# config_headers.net
KiCad netlist of a schematic drawn in Altium Designer
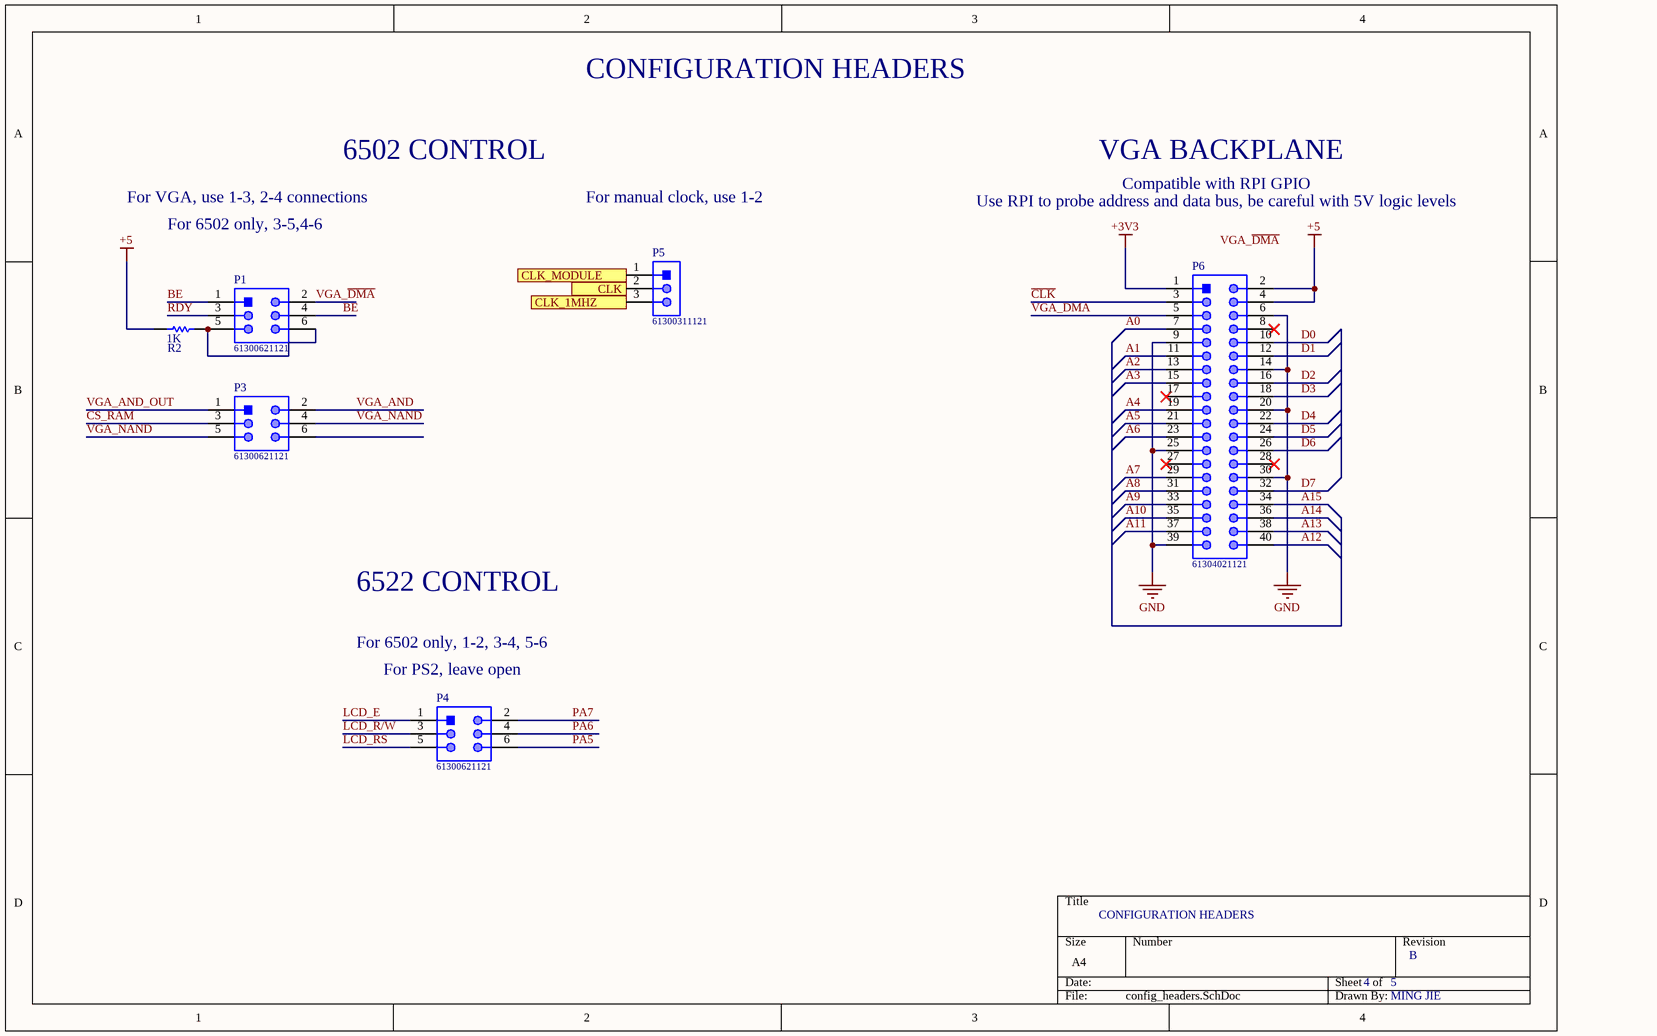
[diagram p0: config_headers.SchDoc]

(export (version "E")
  (design (tool "Eeschema 10.0.6"))
  (components
    (comp (ref "P1")
      (value "61300621121")
      (footprint "61300621121")
      (description "THT Vertical Pin Header WR-PHD, Pitch 2.54 mm, Dual Row, 6 pins")
      (fields (field (name "MANUFACTURER") "Wurth Elektronik") (field (name "PUBLISHER") "WurthElektronik"))
      (libsource (lib "Altium Content Vault") (part "WE-CN-2P-M-R6"))
    )
    (comp (ref "P3")
      (value "61300621121")
      (footprint "61300621121")
      (description "THT Vertical Pin Header WR-PHD, Pitch 2.54 mm, Dual Row, 6 pins")
      (fields (field (name "MANUFACTURER") "Wurth Elektronik") (field (name "PUBLISHER") "WurthElektronik"))
      (libsource (lib "Altium Content Vault") (part "WE-CN-2P-M-R6"))
    )
    (comp (ref "P4")
      (value "61300621121")
      (footprint "61300621121")
      (description "THT Vertical Pin Header WR-PHD, Pitch 2.54 mm, Dual Row, 6 pins")
      (fields (field (name "MANUFACTURER") "Wurth Elektronik") (field (name "PUBLISHER") "WurthElektronik"))
      (libsource (lib "Altium Content Vault") (part "WE-CN-2P-M-R6"))
    )
    (comp (ref "P5")
      (value "61300311121")
      (footprint "61300311121")
      (description "THT Vertical Pin Header WR-PHD, Pitch 2.54 mm, Single Row, 3 pins")
      (fields (field (name "MANUFACTURER") "Wurth Elektronik") (field (name "PUBLISHER") "WurthElektronik"))
      (libsource (lib "Altium Content Vault") (part "WE-CN-1P-M-R3"))
    )
    (comp (ref "P6")
      (value "61304021121")
      (footprint "61304021121")
      (description "THT Vertical Pin Header WR-PHD, Pitch 2.54 mm, Dual Row, 40 pins")
      (fields (field (name "MANUFACTURER") "Wurth Elektronik") (field (name "PUBLISHER") "WurthElektronik"))
      (libsource (lib "Altium Content Vault") (part "WE-CN-2P-M-R40"))
    )
    (comp (ref "R2")
      (value "CRCW08051K00FKEA")
      (footprint "RESC2013X50X30NL20T20")
      (fields (field (name "MANUFACTURER") "Vishay Dale") (field (name "RESISTANCE") "1K"))
      (libsource (lib "Altium Content Vault") (part "RES"))
    )
  )
  (nets
    (net (code "1") (name "+3V3") (class "Default")
      (node (ref "P6") (pin "1") (pinfunction "1_1") (pintype "passive"))
    )
    (net (code "2") (name "+5") (class "Default")
      (node (ref "P6") (pin "2") (pinfunction "2_2") (pintype "passive"))
      (node (ref "P6") (pin "4") (pinfunction "4_4") (pintype "passive"))
      (node (ref "R2") (pin "1") (pinfunction "1_1") (pintype "passive"))
    )
    (net (code "3") (name "/A0") (class "Default")
      (node (ref "P6") (pin "7") (pinfunction "7_7") (pintype "passive"))
    )
    (net (code "4") (name "/A1") (class "Default")
      (node (ref "P6") (pin "11") (pinfunction "11_11") (pintype "passive"))
    )
    (net (code "5") (name "/A2") (class "Default")
      (node (ref "P6") (pin "13") (pinfunction "13_13") (pintype "passive"))
    )
    (net (code "6") (name "/A3") (class "Default")
      (node (ref "P6") (pin "15") (pinfunction "15_15") (pintype "passive"))
    )
    (net (code "7") (name "/A4") (class "Default")
      (node (ref "P6") (pin "19") (pinfunction "19_19") (pintype "passive"))
    )
    (net (code "8") (name "/A5") (class "Default")
      (node (ref "P6") (pin "21") (pinfunction "21_21") (pintype "passive"))
    )
    (net (code "9") (name "/A6") (class "Default")
      (node (ref "P6") (pin "23") (pinfunction "23_23") (pintype "passive"))
    )
    (net (code "10") (name "/A7") (class "Default")
      (node (ref "P6") (pin "29") (pinfunction "29_29") (pintype "passive"))
    )
    (net (code "11") (name "/A8") (class "Default")
      (node (ref "P6") (pin "31") (pinfunction "31_31") (pintype "passive"))
    )
    (net (code "12") (name "/A9") (class "Default")
      (node (ref "P6") (pin "33") (pinfunction "33_33") (pintype "passive"))
    )
    (net (code "13") (name "/A10") (class "Default")
      (node (ref "P6") (pin "35") (pinfunction "35_35") (pintype "passive"))
    )
    (net (code "14") (name "/A11") (class "Default")
      (node (ref "P6") (pin "37") (pinfunction "37_37") (pintype "passive"))
    )
    (net (code "15") (name "/A12") (class "Default")
      (node (ref "P6") (pin "40") (pinfunction "40_40") (pintype "passive"))
    )
    (net (code "16") (name "/A13") (class "Default")
      (node (ref "P6") (pin "38") (pinfunction "38_38") (pintype "passive"))
    )
    (net (code "17") (name "/A14") (class "Default")
      (node (ref "P6") (pin "36") (pinfunction "36_36") (pintype "passive"))
    )
    (net (code "18") (name "/A15") (class "Default")
      (node (ref "P6") (pin "34") (pinfunction "34_34") (pintype "passive"))
    )
    (net (code "19") (name "/BE") (class "Default")
      (node (ref "P1") (pin "1") (pinfunction "1_1") (pintype "passive"))
      (node (ref "P1") (pin "4") (pinfunction "4_4") (pintype "passive"))
    )
    (net (code "20") (name "/CLK") (class "Default")
      (node (ref "P5") (pin "2") (pinfunction "2_2") (pintype "passive"))
    )
    (net (code "21") (name "/CLK_1MHZ") (class "Default")
      (node (ref "P5") (pin "3") (pinfunction "3_3") (pintype "passive"))
    )
    (net (code "22") (name "/CLK_MODULE") (class "Default")
      (node (ref "P5") (pin "1") (pinfunction "1_1") (pintype "passive"))
    )
    (net (code "23") (name "/D0") (class "Default")
      (node (ref "P6") (pin "10") (pinfunction "10_10") (pintype "passive"))
    )
    (net (code "24") (name "/D1") (class "Default")
      (node (ref "P6") (pin "12") (pinfunction "12_12") (pintype "passive"))
    )
    (net (code "25") (name "/D2") (class "Default")
      (node (ref "P6") (pin "16") (pinfunction "16_16") (pintype "passive"))
    )
    (net (code "26") (name "/D3") (class "Default")
      (node (ref "P6") (pin "18") (pinfunction "18_18") (pintype "passive"))
    )
    (net (code "27") (name "/D4") (class "Default")
      (node (ref "P6") (pin "22") (pinfunction "22_22") (pintype "passive"))
    )
    (net (code "28") (name "/D5") (class "Default")
      (node (ref "P6") (pin "24") (pinfunction "24_24") (pintype "passive"))
    )
    (net (code "29") (name "/D6") (class "Default")
      (node (ref "P6") (pin "26") (pinfunction "26_26") (pintype "passive"))
    )
    (net (code "30") (name "/D7") (class "Default")
      (node (ref "P6") (pin "32") (pinfunction "32_32") (pintype "passive"))
    )
    (net (code "31") (name "/LCD_E") (class "Default")
      (node (ref "P4") (pin "1") (pinfunction "1_1") (pintype "passive"))
    )
    (net (code "32") (name "/LCD_RS") (class "Default")
      (node (ref "P4") (pin "5") (pinfunction "5_5") (pintype "passive"))
    )
    (net (code "33") (name "/LCD_R{slash}~{W}") (class "Default")
      (node (ref "P4") (pin "3") (pinfunction "3_3") (pintype "passive"))
    )
    (net (code "34") (name "/PA5") (class "Default")
      (node (ref "P4") (pin "6") (pinfunction "6_6") (pintype "passive"))
    )
    (net (code "35") (name "/PA6") (class "Default")
      (node (ref "P4") (pin "4") (pinfunction "4_4") (pintype "passive"))
    )
    (net (code "36") (name "/PA7") (class "Default")
      (node (ref "P4") (pin "2") (pinfunction "2_2") (pintype "passive"))
    )
    (net (code "37") (name "/RDY") (class "Default")
      (node (ref "P1") (pin "3") (pinfunction "3_3") (pintype "passive"))
    )
    (net (code "38") (name "/VGA_AND") (class "Default")
      (node (ref "P3") (pin "2") (pinfunction "2_2") (pintype "passive"))
    )
    (net (code "39") (name "/VGA_AND_OUT") (class "Default")
      (node (ref "P3") (pin "1") (pinfunction "1_1") (pintype "passive"))
    )
    (net (code "40") (name "/VGA_NAND") (class "Default")
      (node (ref "P3") (pin "4") (pinfunction "4_4") (pintype "passive"))
      (node (ref "P3") (pin "5") (pinfunction "5_5") (pintype "passive"))
    )
    (net (code "41") (name "/VGA_~{DMA}") (class "Default")
      (node (ref "P1") (pin "2") (pinfunction "2_2") (pintype "passive"))
      (node (ref "P6") (pin "5") (pinfunction "5_5") (pintype "passive"))
    )
    (net (code "42") (name "/~{CLK}") (class "Default")
      (node (ref "P6") (pin "3") (pinfunction "3_3") (pintype "passive"))
    )
    (net (code "43") (name "/~{CS}_RAM") (class "Default")
      (node (ref "P3") (pin "3") (pinfunction "3_3") (pintype "passive"))
    )
    (net (code "44") (name "GND") (class "Default")
      (node (ref "P6") (pin "14") (pinfunction "14_14") (pintype "passive"))
      (node (ref "P6") (pin "20") (pinfunction "20_20") (pintype "passive"))
      (node (ref "P6") (pin "25") (pinfunction "25_25") (pintype "passive"))
      (node (ref "P6") (pin "30") (pinfunction "30_30") (pintype "passive"))
      (node (ref "P6") (pin "39") (pinfunction "39_39") (pintype "passive"))
      (node (ref "P6") (pin "6") (pinfunction "6_6") (pintype "passive"))
      (node (ref "P6") (pin "9") (pinfunction "9_9") (pintype "passive"))
    )
    (net (code "45") (name "Net-(P1-Pad5)") (class "Default")
      (node (ref "P1") (pin "5") (pinfunction "5_5") (pintype "passive"))
      (node (ref "P1") (pin "6") (pinfunction "6_6") (pintype "passive"))
      (node (ref "R2") (pin "2") (pinfunction "2_2") (pintype "passive"))
    )
    (net (code "46") (name "unconnected-(P3-Pad6)") (class "Default")
      (node (ref "P3") (pin "6") (pinfunction "6_6") (pintype "passive"))
    )
    (net (code "47") (name "unconnected-(P6-Pad8)") (class "Default")
      (node (ref "P6") (pin "8") (pinfunction "8_8") (pintype "passive+no_connect"))
    )
    (net (code "48") (name "unconnected-(P6-Pad17)") (class "Default")
      (node (ref "P6") (pin "17") (pinfunction "17_17") (pintype "passive+no_connect"))
    )
    (net (code "49") (name "unconnected-(P6-Pad27)") (class "Default")
      (node (ref "P6") (pin "27") (pinfunction "27_27") (pintype "passive+no_connect"))
    )
    (net (code "50") (name "unconnected-(P6-Pad28)") (class "Default")
      (node (ref "P6") (pin "28") (pinfunction "28_28") (pintype "passive+no_connect"))
    )
  )
)
